# User_Interface.net
KiCad netlist of a schematic drawn in Altium Designer
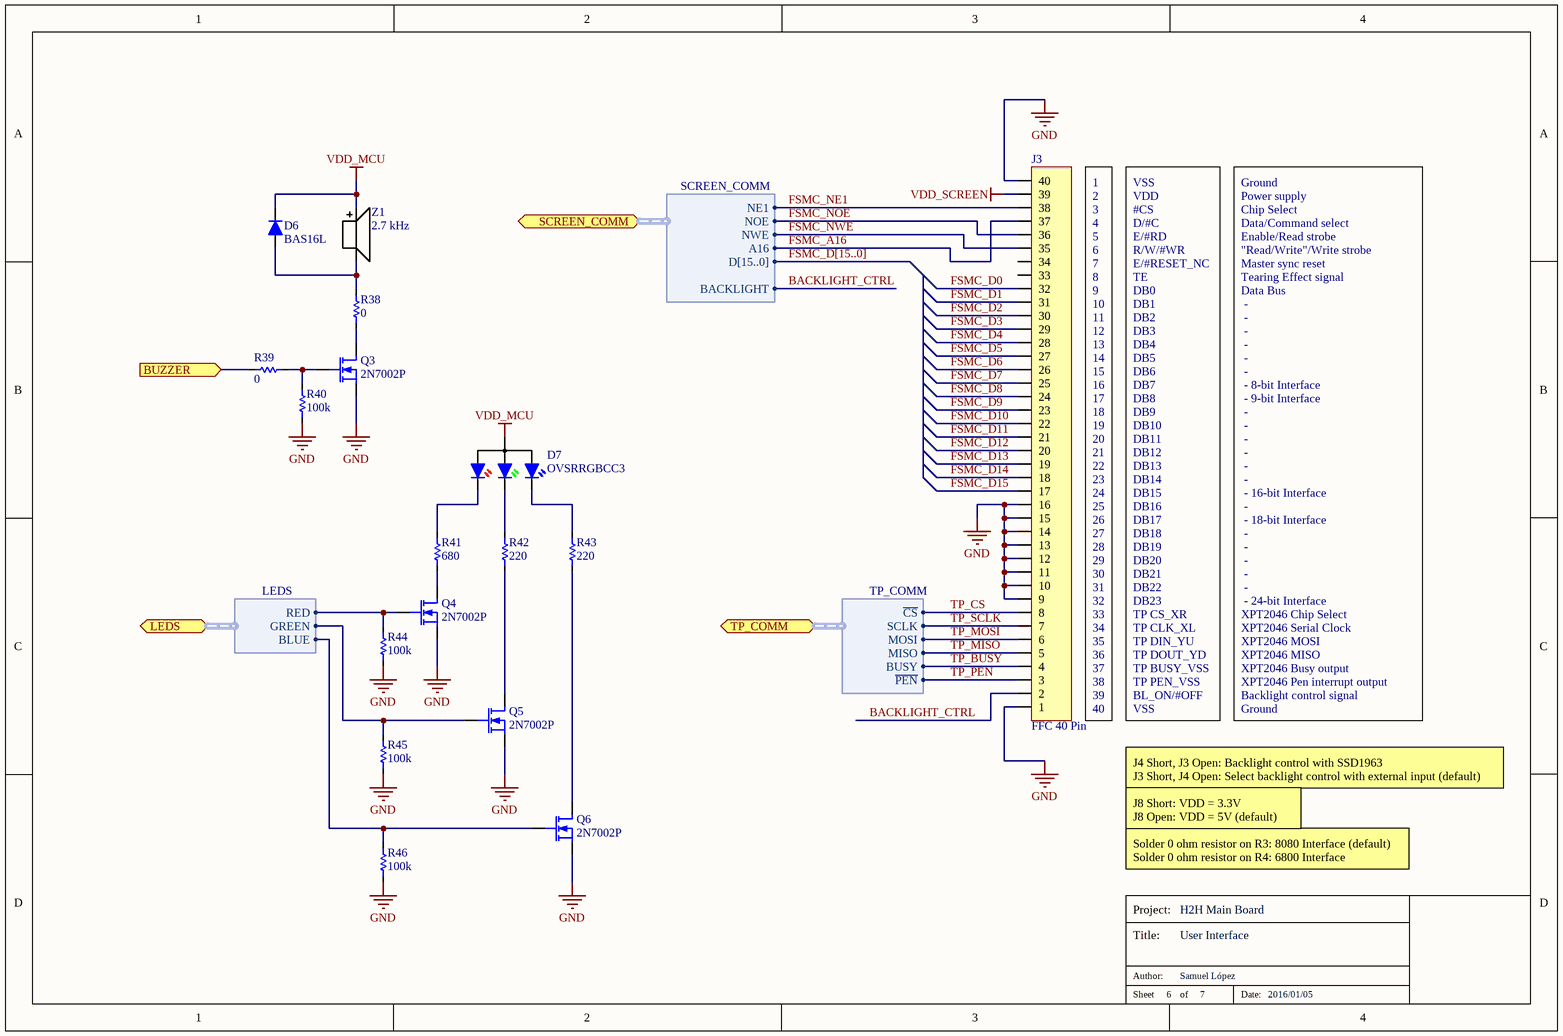
[diagram p0: User Interface.SchDoc]

(export (version "E")
  (design (tool "Eeschema 10.0.6"))
  (components
    (comp (ref "D6")
      (value "BAS16L")
      (footprint "BAS16L")
      (description "Diode - Switching diode, 1 V, 200 mA")
      (libsource (lib "H2H") (part "BAS16L"))
    )
    (comp (ref "D7")
      (value "OVSRRGBCC3")
      (footprint "OVSRRGBCC3/SIDE")
      (description "LED - RGB, Top/Side-emmiting")
      (libsource (lib "H2H") (part "OVSRRGBCC3"))
    )
    (comp (ref "J3")
      (value "FFC 40 Pin")
      (footprint "ER-CON40HB-2")
      (description "Conn - FFC/FPC, 40 Pin, 1.0mm Pitch, ZIF")
      (libsource (lib "Conn") (part "ER-CON40HB-2"))
    )
    (comp (ref "Q3")
      (value "2N7002P")
      (footprint "2N7002P")
      (description "Transistor - MOSFET, N-Channel, 60V, 300mA")
      (libsource (lib "H2H") (part "2N7002P"))
    )
    (comp (ref "Q4")
      (value "2N7002P")
      (footprint "2N7002P")
      (description "Transistor - MOSFET, N-Channel, 60V, 300mA")
      (libsource (lib "H2H") (part "2N7002P"))
    )
    (comp (ref "Q5")
      (value "2N7002P")
      (footprint "2N7002P")
      (description "Transistor - MOSFET, N-Channel, 60V, 300mA")
      (libsource (lib "H2H") (part "2N7002P"))
    )
    (comp (ref "Q6")
      (value "2N7002P")
      (footprint "2N7002P")
      (description "Transistor - MOSFET, N-Channel, 60V, 300mA")
      (libsource (lib "H2H") (part "2N7002P"))
    )
    (comp (ref "R38")
      (value "0")
      (footprint "R0603")
      (description "Resistor")
      (libsource (lib "Misc") (part "Resistor"))
    )
    (comp (ref "R39")
      (value "0")
      (footprint "R0603")
      (description "Resistor")
      (libsource (lib "Misc") (part "Resistor"))
    )
    (comp (ref "R40")
      (value "100k")
      (footprint "R0603")
      (description "Resistor")
      (libsource (lib "Misc") (part "Resistor"))
    )
    (comp (ref "R41")
      (value "680")
      (footprint "R0603")
      (description "Resistor")
      (libsource (lib "Misc") (part "Resistor"))
    )
    (comp (ref "R42")
      (value "220")
      (footprint "R0603")
      (description "Resistor")
      (libsource (lib "Misc") (part "Resistor"))
    )
    (comp (ref "R43")
      (value "220")
      (footprint "R0603")
      (description "Resistor")
      (libsource (lib "Misc") (part "Resistor"))
    )
    (comp (ref "R44")
      (value "100k")
      (footprint "R0603")
      (description "Resistor")
      (libsource (lib "Misc") (part "Resistor"))
    )
    (comp (ref "R45")
      (value "100k")
      (footprint "R0603")
      (description "Resistor")
      (libsource (lib "Misc") (part "Resistor"))
    )
    (comp (ref "R46")
      (value "100k")
      (footprint "R0603")
      (description "Resistor")
      (libsource (lib "Misc") (part "Resistor"))
    )
    (comp (ref "Z1")
      (value "2.7 kHz")
      (footprint "KSSG74B16")
      (description "Transductor - Buzzer 2.7 kHz")
      (libsource (lib "H2H") (part "KSSG74B16"))
    )
  )
  (nets
    (net (code "4") (name "/BACKLIGHT_CTRL") (class "Default")
      (node (ref "J3") (pin "2") (pinfunction "2_2") (pintype "passive"))
    )
    (net (code "5") (name "/BUZZER") (class "Default")
      (node (ref "R39") (pin "1") (pinfunction "1_1") (pintype "passive"))
    )
    (net (code "6") (name "/FSMC_A16") (class "Default")
      (node (ref "J3") (pin "37") (pinfunction "37_37") (pintype "passive"))
    )
    (net (code "7") (name "/FSMC_D0") (class "Default")
      (node (ref "J3") (pin "32") (pinfunction "32_32") (pintype "passive"))
    )
    (net (code "8") (name "/FSMC_D1") (class "Default")
      (node (ref "J3") (pin "31") (pinfunction "31_31") (pintype "passive"))
    )
    (net (code "9") (name "/FSMC_D2") (class "Default")
      (node (ref "J3") (pin "30") (pinfunction "30_30") (pintype "passive"))
    )
    (net (code "10") (name "/FSMC_D3") (class "Default")
      (node (ref "J3") (pin "29") (pinfunction "29_29") (pintype "passive"))
    )
    (net (code "11") (name "/FSMC_D4") (class "Default")
      (node (ref "J3") (pin "28") (pinfunction "28_28") (pintype "passive"))
    )
    (net (code "12") (name "/FSMC_D5") (class "Default")
      (node (ref "J3") (pin "27") (pinfunction "27_27") (pintype "passive"))
    )
    (net (code "13") (name "/FSMC_D6") (class "Default")
      (node (ref "J3") (pin "26") (pinfunction "26_26") (pintype "passive"))
    )
    (net (code "14") (name "/FSMC_D7") (class "Default")
      (node (ref "J3") (pin "25") (pinfunction "25_25") (pintype "passive"))
    )
    (net (code "15") (name "/FSMC_D8") (class "Default")
      (node (ref "J3") (pin "24") (pinfunction "24_24") (pintype "passive"))
    )
    (net (code "16") (name "/FSMC_D9") (class "Default")
      (node (ref "J3") (pin "23") (pinfunction "23_23") (pintype "passive"))
    )
    (net (code "17") (name "/FSMC_D10") (class "Default")
      (node (ref "J3") (pin "22") (pinfunction "22_22") (pintype "passive"))
    )
    (net (code "18") (name "/FSMC_D11") (class "Default")
      (node (ref "J3") (pin "21") (pinfunction "21_21") (pintype "passive"))
    )
    (net (code "19") (name "/FSMC_D12") (class "Default")
      (node (ref "J3") (pin "20") (pinfunction "20_20") (pintype "passive"))
    )
    (net (code "20") (name "/FSMC_D13") (class "Default")
      (node (ref "J3") (pin "19") (pinfunction "19_19") (pintype "passive"))
    )
    (net (code "21") (name "/FSMC_D14") (class "Default")
      (node (ref "J3") (pin "18") (pinfunction "18_18") (pintype "passive"))
    )
    (net (code "22") (name "/FSMC_D15") (class "Default")
      (node (ref "J3") (pin "17") (pinfunction "17_17") (pintype "passive"))
    )
    (net (code "23") (name "/FSMC_NE1") (class "Default")
      (node (ref "J3") (pin "38") (pinfunction "38_38") (pintype "passive"))
    )
    (net (code "24") (name "/FSMC_NOE") (class "Default")
      (node (ref "J3") (pin "36") (pinfunction "36_36") (pintype "passive"))
    )
    (net (code "25") (name "/FSMC_NWE") (class "Default")
      (node (ref "J3") (pin "35") (pinfunction "35_35") (pintype "passive"))
    )
    (net (code "27") (name "/TP_BUSY") (class "Default")
      (node (ref "J3") (pin "4") (pinfunction "4_4") (pintype "passive"))
    )
    (net (code "28") (name "/TP_CS") (class "Default")
      (node (ref "J3") (pin "8") (pinfunction "8_8") (pintype "passive"))
    )
    (net (code "29") (name "/TP_MISO") (class "Default")
      (node (ref "J3") (pin "5") (pinfunction "5_5") (pintype "passive"))
    )
    (net (code "30") (name "/TP_MOSI") (class "Default")
      (node (ref "J3") (pin "6") (pinfunction "6_6") (pintype "passive"))
    )
    (net (code "31") (name "/TP_PEN") (class "Default")
      (node (ref "J3") (pin "3") (pinfunction "3_3") (pintype "passive"))
    )
    (net (code "32") (name "/TP_SCLK") (class "Default")
      (node (ref "J3") (pin "7") (pinfunction "7_7") (pintype "passive"))
    )
    (net (code "36") (name "GND") (class "Default")
      (node (ref "J3") (pin "1") (pinfunction "1_1") (pintype "passive"))
      (node (ref "J3") (pin "10") (pinfunction "10_10") (pintype "passive"))
      (node (ref "J3") (pin "11") (pinfunction "11_11") (pintype "passive"))
      (node (ref "J3") (pin "12") (pinfunction "12_12") (pintype "passive"))
      (node (ref "J3") (pin "13") (pinfunction "13_13") (pintype "passive"))
      (node (ref "J3") (pin "14") (pinfunction "14_14") (pintype "passive"))
      (node (ref "J3") (pin "15") (pinfunction "15_15") (pintype "passive"))
      (node (ref "J3") (pin "16") (pinfunction "16_16") (pintype "passive"))
      (node (ref "J3") (pin "40") (pinfunction "40_40") (pintype "passive"))
      (node (ref "J3") (pin "9") (pinfunction "9_9") (pintype "passive"))
      (node (ref "Q3") (pin "2") (pinfunction "S_2") (pintype "passive"))
      (node (ref "Q4") (pin "2") (pinfunction "S_2") (pintype "passive"))
      (node (ref "Q5") (pin "2") (pinfunction "S_2") (pintype "passive"))
      (node (ref "Q6") (pin "2") (pinfunction "S_2") (pintype "passive"))
      (node (ref "R40") (pin "2") (pinfunction "2_2") (pintype "passive"))
      (node (ref "R44") (pin "2") (pinfunction "2_2") (pintype "passive"))
      (node (ref "R45") (pin "2") (pinfunction "2_2") (pintype "passive"))
      (node (ref "R46") (pin "2") (pinfunction "2_2") (pintype "passive"))
    )
    (net (code "37") (name "Net-(D6-A)") (class "Default")
      (node (ref "D6") (pin "1") (pinfunction "A_1") (pintype "passive"))
      (node (ref "R38") (pin "1") (pinfunction "1_1") (pintype "passive"))
      (node (ref "Z1") (pin "2") (pinfunction "-_2") (pintype "passive"))
    )
    (net (code "38") (name "Net-(D7-K_B)") (class "Default")
      (node (ref "D7") (pin "3") (pinfunction "K_B_3") (pintype "passive"))
      (node (ref "R43") (pin "2") (pinfunction "2_2") (pintype "passive"))
    )
    (net (code "39") (name "Net-(D7-K_G)") (class "Default")
      (node (ref "D7") (pin "2") (pinfunction "K_G_2") (pintype "passive"))
      (node (ref "R42") (pin "1") (pinfunction "1_1") (pintype "passive"))
    )
    (net (code "40") (name "Net-(D7-K_R)") (class "Default")
      (node (ref "D7") (pin "1") (pinfunction "K_R_1") (pintype "passive"))
      (node (ref "R41") (pin "2") (pinfunction "2_2") (pintype "passive"))
    )
    (net (code "41") (name "Net-(Q3-D)") (class "Default")
      (node (ref "Q3") (pin "3") (pinfunction "D_3") (pintype "passive"))
      (node (ref "R38") (pin "2") (pinfunction "2_2") (pintype "passive"))
    )
    (net (code "42") (name "Net-(Q3-G)") (class "Default")
      (node (ref "Q3") (pin "1") (pinfunction "G_1") (pintype "passive"))
      (node (ref "R39") (pin "2") (pinfunction "2_2") (pintype "passive"))
      (node (ref "R40") (pin "1") (pinfunction "1_1") (pintype "passive"))
    )
    (net (code "43") (name "Net-(Q4-D)") (class "Default")
      (node (ref "Q4") (pin "3") (pinfunction "D_3") (pintype "passive"))
      (node (ref "R41") (pin "1") (pinfunction "1_1") (pintype "passive"))
    )
    (net (code "44") (name "Net-(Q4-G)") (class "Default")
      (node (ref "Q4") (pin "1") (pinfunction "G_1") (pintype "passive"))
      (node (ref "R44") (pin "1") (pinfunction "1_1") (pintype "passive"))
    )
    (net (code "45") (name "Net-(Q5-D)") (class "Default")
      (node (ref "Q5") (pin "3") (pinfunction "D_3") (pintype "passive"))
      (node (ref "R42") (pin "2") (pinfunction "2_2") (pintype "passive"))
    )
    (net (code "46") (name "Net-(Q5-G)") (class "Default")
      (node (ref "Q5") (pin "1") (pinfunction "G_1") (pintype "passive"))
      (node (ref "R45") (pin "1") (pinfunction "1_1") (pintype "passive"))
    )
    (net (code "47") (name "Net-(Q6-D)") (class "Default")
      (node (ref "Q6") (pin "3") (pinfunction "D_3") (pintype "passive"))
      (node (ref "R43") (pin "1") (pinfunction "1_1") (pintype "passive"))
    )
    (net (code "48") (name "Net-(Q6-G)") (class "Default")
      (node (ref "Q6") (pin "1") (pinfunction "G_1") (pintype "passive"))
      (node (ref "R46") (pin "1") (pinfunction "1_1") (pintype "passive"))
    )
    (net (code "49") (name "VDD_MCU") (class "Default")
      (node (ref "D6") (pin "3") (pinfunction "K_3") (pintype "passive"))
      (node (ref "D7") (pin "4") (pinfunction "A_4") (pintype "passive"))
      (node (ref "Z1") (pin "1") (pinfunction "+_1") (pintype "passive"))
    )
    (net (code "50") (name "VDD_SCREEN") (class "Default")
      (node (ref "J3") (pin "39") (pinfunction "39_39") (pintype "passive"))
    )
    (net (code "51") (name "unconnected-(J3-Pad33)") (class "Default")
      (node (ref "J3") (pin "33") (pinfunction "33_33") (pintype "passive"))
    )
    (net (code "52") (name "unconnected-(J3-Pad34)") (class "Default")
      (node (ref "J3") (pin "34") (pinfunction "34_34") (pintype "passive"))
    )
  )
)
